# G-CLEF_Shutter_Testing.net
KiCad netlist of a schematic drawn in EAGLE
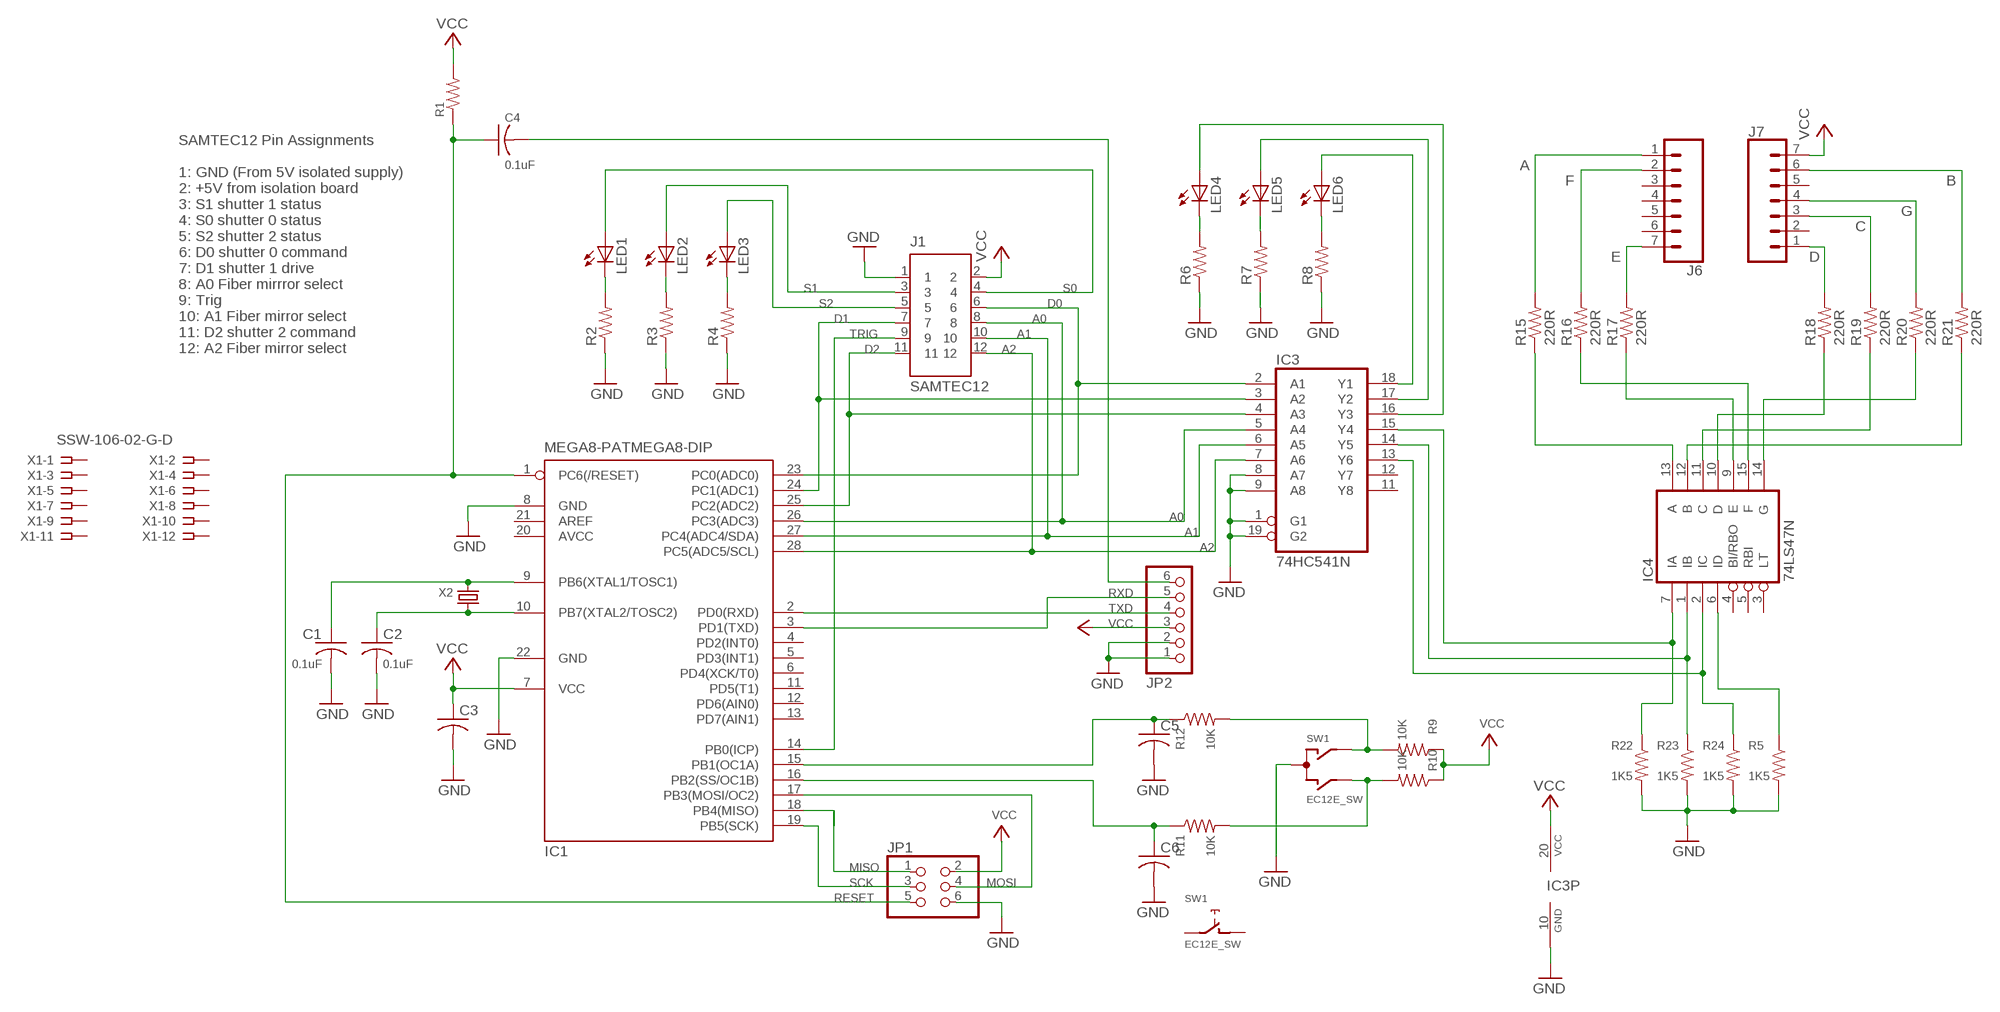
[diagram p0: schematic, sheet 1, part 1 of 2]
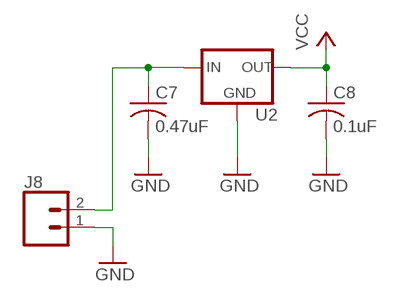
[diagram p1: schematic, sheet 1, part 2 of 2]

(export (version "E")
  (design (tool "Eeschema 10.0.6"))
  (components
    (comp (ref "C1")
      (value "0.1uF")
      (footprint "eagle-import:C025-024X044")
      (libsource (lib "eagle-import") (part "C-US025-024X044"))
    )
    (comp (ref "C2")
      (value "0.1uF")
      (footprint "eagle-import:C025-024X044")
      (libsource (lib "eagle-import") (part "C-US025-024X044"))
    )
    (comp (ref "C3")
      (value "C-US025-024X044")
      (footprint "eagle-import:C025-024X044")
      (libsource (lib "eagle-import") (part "C-US025-024X044"))
    )
    (comp (ref "C4")
      (value "0.1uF")
      (footprint "eagle-import:C025-024X044")
      (libsource (lib "eagle-import") (part "C-US025-024X044"))
    )
    (comp (ref "C5")
      (value "C-US025-024X044")
      (footprint "eagle-import:C025-024X044")
      (libsource (lib "eagle-import") (part "C-US025-024X044"))
    )
    (comp (ref "C6")
      (value "C-US025-024X044")
      (footprint "eagle-import:C025-024X044")
      (libsource (lib "eagle-import") (part "C-US025-024X044"))
    )
    (comp (ref "C7")
      (value "0.47uF")
      (footprint "eagle-import:C050-025X075")
      (libsource (lib "eagle-import") (part "rcl_334_C-US050-025X075"))
    )
    (comp (ref "C8")
      (value "0.1uF")
      (footprint "eagle-import:C050-025X075")
      (libsource (lib "eagle-import") (part "rcl_334_C-US050-025X075"))
    )
    (comp (ref "IC1")
      (value "MEGA8-PATMEGA8-DIP")
      (footprint "eagle-import:DIP762W53P254L3467H457Q28B")
      (libsource (lib "eagle-import") (part "MEGA8-PATMEGA8-DIP"))
    )
    (comp (ref "IC3")
      (value "74HC541N")
      (footprint "eagle-import:DIL20")
      (libsource (lib "eagle-import") (part "74541NLS"))
    )
    (comp (ref "IC4")
      (value "74LS47N")
      (footprint "eagle-import:DIL16")
      (libsource (lib "eagle-import") (part "7447NLS"))
    )
    (comp (ref "J1")
      (value "SAMTEC12")
      (footprint "eagle-import:SAMTEC12")
      (libsource (lib "eagle-import") (part "SAMTEC12"))
    )
    (comp (ref "J6")
      (value "CONN_07")
      (footprint "eagle-import:1X07")
      (libsource (lib "eagle-import") (part "CONN_07"))
    )
    (comp (ref "J7")
      (value "CONN_07")
      (footprint "eagle-import:1X07")
      (libsource (lib "eagle-import") (part "CONN_07"))
    )
    (comp (ref "J8")
      (value "CONN_02")
      (footprint "eagle-import:1X02")
      (libsource (lib "eagle-import") (part "CONN_02"))
    )
    (comp (ref "JP1")
      (value "PINHD-2X3")
      (footprint "eagle-import:2X03")
      (libsource (lib "eagle-import") (part "PINHD-2X3"))
    )
    (comp (ref "JP2")
      (value "PINHD-1X6/90")
      (footprint "eagle-import:1X06_90")
      (libsource (lib "eagle-import") (part "PINHD-1X6/90"))
    )
    (comp (ref "LED1")
      (value "LED5MM")
      (footprint "eagle-import:LED5MM")
      (libsource (lib "eagle-import") (part "LED5MM"))
    )
    (comp (ref "LED2")
      (value "LED5MM")
      (footprint "eagle-import:LED5MM")
      (libsource (lib "eagle-import") (part "LED5MM"))
    )
    (comp (ref "LED3")
      (value "LED5MM")
      (footprint "eagle-import:LED5MM")
      (libsource (lib "eagle-import") (part "LED5MM"))
    )
    (comp (ref "LED4")
      (value "LED5MM")
      (footprint "eagle-import:LED5MM")
      (libsource (lib "eagle-import") (part "LED5MM"))
    )
    (comp (ref "LED5")
      (value "LED5MM")
      (footprint "eagle-import:LED5MM")
      (libsource (lib "eagle-import") (part "LED5MM"))
    )
    (comp (ref "LED6")
      (value "LED5MM")
      (footprint "eagle-import:LED5MM")
      (libsource (lib "eagle-import") (part "LED5MM"))
    )
    (comp (ref "R1")
      (value "R-US_0207/7")
      (footprint "eagle-import:0207_7")
      (libsource (lib "eagle-import") (part "R-US_0207/7"))
    )
    (comp (ref "R2")
      (value "R-US_0207/7")
      (footprint "eagle-import:0207_7")
      (libsource (lib "eagle-import") (part "R-US_0207/7"))
    )
    (comp (ref "R3")
      (value "R-US_0207/7")
      (footprint "eagle-import:0207_7")
      (libsource (lib "eagle-import") (part "R-US_0207/7"))
    )
    (comp (ref "R4")
      (value "R-US_0207/7")
      (footprint "eagle-import:0207_7")
      (libsource (lib "eagle-import") (part "R-US_0207/7"))
    )
    (comp (ref "R5")
      (value "1K5")
      (footprint "eagle-import:0207_7")
      (libsource (lib "eagle-import") (part "rcl_334_R-US_0207/7"))
    )
    (comp (ref "R6")
      (value "R-US_0207/7")
      (footprint "eagle-import:0207_7")
      (libsource (lib "eagle-import") (part "R-US_0207/7"))
    )
    (comp (ref "R7")
      (value "R-US_0207/7")
      (footprint "eagle-import:0207_7")
      (libsource (lib "eagle-import") (part "R-US_0207/7"))
    )
    (comp (ref "R8")
      (value "R-US_0207/7")
      (footprint "eagle-import:0207_7")
      (libsource (lib "eagle-import") (part "R-US_0207/7"))
    )
    (comp (ref "R9")
      (value "10K")
      (footprint "eagle-import:0207_7")
      (libsource (lib "eagle-import") (part "rcl_334_R-US_0207/7"))
    )
    (comp (ref "R10")
      (value "10K")
      (footprint "eagle-import:0207_7")
      (libsource (lib "eagle-import") (part "rcl_334_R-US_0207/7"))
    )
    (comp (ref "R11")
      (value "10K")
      (footprint "eagle-import:0207_7")
      (libsource (lib "eagle-import") (part "rcl_334_R-US_0207/7"))
    )
    (comp (ref "R12")
      (value "10K")
      (footprint "eagle-import:0207_7")
      (libsource (lib "eagle-import") (part "rcl_334_R-US_0207/7"))
    )
    (comp (ref "R15")
      (value "220R")
      (footprint "eagle-import:0207_7")
      (libsource (lib "eagle-import") (part "rcl_334_R-US_0207/7"))
    )
    (comp (ref "R16")
      (value "220R")
      (footprint "eagle-import:0207_7")
      (libsource (lib "eagle-import") (part "rcl_334_R-US_0207/7"))
    )
    (comp (ref "R17")
      (value "220R")
      (footprint "eagle-import:0207_7")
      (libsource (lib "eagle-import") (part "rcl_334_R-US_0207/7"))
    )
    (comp (ref "R18")
      (value "220R")
      (footprint "eagle-import:0207_7")
      (libsource (lib "eagle-import") (part "rcl_334_R-US_0207/7"))
    )
    (comp (ref "R19")
      (value "220R")
      (footprint "eagle-import:0207_7")
      (libsource (lib "eagle-import") (part "rcl_334_R-US_0207/7"))
    )
    (comp (ref "R20")
      (value "220R")
      (footprint "eagle-import:0207_7")
      (libsource (lib "eagle-import") (part "rcl_334_R-US_0207/7"))
    )
    (comp (ref "R21")
      (value "220R")
      (footprint "eagle-import:0207_7")
      (libsource (lib "eagle-import") (part "rcl_334_R-US_0207/7"))
    )
    (comp (ref "R22")
      (value "1K5")
      (footprint "eagle-import:0207_7")
      (libsource (lib "eagle-import") (part "rcl_334_R-US_0207/7"))
    )
    (comp (ref "R23")
      (value "1K5")
      (footprint "eagle-import:0207_7")
      (libsource (lib "eagle-import") (part "rcl_334_R-US_0207/7"))
    )
    (comp (ref "R24")
      (value "1K5")
      (footprint "eagle-import:0207_7")
      (libsource (lib "eagle-import") (part "rcl_334_R-US_0207/7"))
    )
    (comp (ref "SW1")
      (value "EC12E_SW")
      (footprint "eagle-import:ALPS_EC12E_SW")
      (fields (field (name "MPN") "EC12E2424407"))
      (libsource (lib "eagle-import") (part "EC12E_SW"))
    )
    (comp (ref "U2")
      (value "V_REG_78XXSINK")
      (footprint "eagle-import:TO220-IGO")
      (libsource (lib "eagle-import") (part "V_REG_78XXSINK"))
    )
    (comp (ref "X1")
      (value "SSW-106-02-G-D")
      (footprint "eagle-import:SSW-106-02-G-D")
      (fields (field (name "MF") "Samtec Inc."))
      (libsource (lib "eagle-import") (part "SSW-106-02-G-D"))
    )
    (comp (ref "X2")
      (value "CRYSTALS-NOGND-HC49")
      (footprint "eagle-import:HC49")
      (libsource (lib "eagle-import") (part "CRYSTALS-NOGND-HC49"))
    )
  )
  (nets
    (net (code "1") (name "/A") (class "Default")
      (node (ref "J6") (pin "1") (pinfunction "1_1") (pintype "passive"))
      (node (ref "R15") (pin "2") (pinfunction "2_2") (pintype "passive"))
    )
    (net (code "2") (name "/A0") (class "Default")
      (node (ref "IC1") (pin "26") (pinfunction "PC3(ADC3)_26") (pintype "bidirectional"))
      (node (ref "IC3") (pin "5") (pinfunction "A4_5") (pintype "input"))
      (node (ref "J1") (pin "8") (pinfunction "8_8") (pintype "bidirectional"))
    )
    (net (code "3") (name "/A1") (class "Default")
      (node (ref "IC1") (pin "27") (pinfunction "PC4(ADC4/SDA)_27") (pintype "bidirectional"))
      (node (ref "IC3") (pin "6") (pinfunction "A5_6") (pintype "input"))
      (node (ref "J1") (pin "10") (pinfunction "10_10") (pintype "bidirectional"))
    )
    (net (code "4") (name "/A2") (class "Default")
      (node (ref "IC1") (pin "28") (pinfunction "PC5(ADC5/SCL)_28") (pintype "bidirectional"))
      (node (ref "IC3") (pin "7") (pinfunction "A6_7") (pintype "input"))
      (node (ref "J1") (pin "12") (pinfunction "12_12") (pintype "bidirectional"))
    )
    (net (code "5") (name "/AVCC") (class "Default")
      (node (ref "IC1") (pin "20") (pinfunction "AVCC_20") (pintype "power_in"))
    )
    (net (code "6") (name "/B") (class "Default")
      (node (ref "J7") (pin "6") (pinfunction "6_6") (pintype "passive"))
      (node (ref "R21") (pin "2") (pinfunction "2_2") (pintype "passive"))
    )
    (net (code "7") (name "/C") (class "Default")
      (node (ref "J7") (pin "3") (pinfunction "3_3") (pintype "passive"))
      (node (ref "R19") (pin "2") (pinfunction "2_2") (pintype "passive"))
    )
    (net (code "8") (name "/D") (class "Default")
      (node (ref "J7") (pin "1") (pinfunction "1_1") (pintype "passive"))
      (node (ref "R18") (pin "2") (pinfunction "2_2") (pintype "passive"))
    )
    (net (code "9") (name "/D0") (class "Default")
      (node (ref "IC1") (pin "23") (pinfunction "PC0(ADC0)_23") (pintype "bidirectional"))
      (node (ref "IC3") (pin "2") (pinfunction "A1_2") (pintype "input"))
      (node (ref "J1") (pin "6") (pinfunction "6_6") (pintype "bidirectional"))
    )
    (net (code "10") (name "/D1") (class "Default")
      (node (ref "IC1") (pin "24") (pinfunction "PC1(ADC1)_24") (pintype "bidirectional"))
      (node (ref "IC3") (pin "3") (pinfunction "A2_3") (pintype "input"))
      (node (ref "J1") (pin "7") (pinfunction "7_7") (pintype "bidirectional"))
    )
    (net (code "11") (name "/D2") (class "Default")
      (node (ref "IC1") (pin "25") (pinfunction "PC2(ADC2)_25") (pintype "bidirectional"))
      (node (ref "IC3") (pin "4") (pinfunction "A3_4") (pintype "input"))
      (node (ref "J1") (pin "11") (pinfunction "11_11") (pintype "bidirectional"))
    )
    (net (code "12") (name "/E") (class "Default")
      (node (ref "J6") (pin "7") (pinfunction "7_7") (pintype "passive"))
      (node (ref "R17") (pin "2") (pinfunction "2_2") (pintype "passive"))
    )
    (net (code "13") (name "/F") (class "Default")
      (node (ref "J6") (pin "2") (pinfunction "2_2") (pintype "passive"))
      (node (ref "R16") (pin "2") (pinfunction "2_2") (pintype "passive"))
    )
    (net (code "14") (name "/G") (class "Default")
      (node (ref "J7") (pin "4") (pinfunction "4_4") (pintype "passive"))
      (node (ref "R20") (pin "2") (pinfunction "2_2") (pintype "passive"))
    )
    (net (code "15") (name "/MISO") (class "Default")
      (node (ref "IC1") (pin "18") (pinfunction "PB4(MISO)_18") (pintype "bidirectional"))
      (node (ref "JP1") (pin "1") (pinfunction "1_1") (pintype "passive"))
    )
    (net (code "16") (name "/MOSI") (class "Default")
      (node (ref "IC1") (pin "17") (pinfunction "PB3(MOSI/OC2)_17") (pintype "bidirectional"))
      (node (ref "JP1") (pin "4") (pinfunction "4_4") (pintype "passive"))
    )
    (net (code "17") (name "/RESET") (class "Default")
      (node (ref "C4") (pin "1") (pinfunction "1_1") (pintype "passive"))
      (node (ref "IC1") (pin "1") (pinfunction "PC6(/RESET)_1") (pintype "bidirectional"))
      (node (ref "JP1") (pin "5") (pinfunction "5_5") (pintype "passive"))
      (node (ref "R1") (pin "1") (pinfunction "1_1") (pintype "passive"))
    )
    (net (code "18") (name "/RXD") (class "Default")
      (node (ref "IC1") (pin "3") (pinfunction "PD1(TXD)_3") (pintype "bidirectional"))
      (node (ref "JP2") (pin "5") (pinfunction "5_5") (pintype "passive"))
    )
    (net (code "19") (name "/S0") (class "Default")
      (node (ref "J1") (pin "4") (pinfunction "4_4") (pintype "bidirectional"))
      (node (ref "LED1") (pin "A") (pinfunction "A_A") (pintype "passive"))
    )
    (net (code "20") (name "/S1") (class "Default")
      (node (ref "J1") (pin "3") (pinfunction "3_3") (pintype "bidirectional"))
      (node (ref "LED2") (pin "A") (pinfunction "A_A") (pintype "passive"))
    )
    (net (code "21") (name "/S2") (class "Default")
      (node (ref "J1") (pin "5") (pinfunction "5_5") (pintype "bidirectional"))
      (node (ref "LED3") (pin "A") (pinfunction "A_A") (pintype "passive"))
    )
    (net (code "22") (name "/SCK") (class "Default")
      (node (ref "IC1") (pin "19") (pinfunction "PB5(SCK)_19") (pintype "bidirectional"))
      (node (ref "JP1") (pin "3") (pinfunction "3_3") (pintype "passive"))
    )
    (net (code "23") (name "/TRIG") (class "Default")
      (node (ref "IC1") (pin "14") (pinfunction "PB0(ICP)_14") (pintype "bidirectional"))
      (node (ref "J1") (pin "9") (pinfunction "9_9") (pintype "bidirectional"))
    )
    (net (code "24") (name "/TXD") (class "Default")
      (node (ref "IC1") (pin "2") (pinfunction "PD0(RXD)_2") (pintype "bidirectional"))
      (node (ref "JP2") (pin "4") (pinfunction "4_4") (pintype "passive"))
    )
    (net (code "25") (name "GND") (class "Default")
      (node (ref "C1") (pin "2") (pinfunction "2_2") (pintype "passive"))
      (node (ref "C2") (pin "2") (pinfunction "2_2") (pintype "passive"))
      (node (ref "C3") (pin "2") (pinfunction "2_2") (pintype "passive"))
      (node (ref "C5") (pin "2") (pinfunction "2_2") (pintype "passive"))
      (node (ref "C6") (pin "2") (pinfunction "2_2") (pintype "passive"))
      (node (ref "C7") (pin "2") (pinfunction "2_2") (pintype "passive"))
      (node (ref "C8") (pin "2") (pinfunction "2_2") (pintype "passive"))
      (node (ref "IC1") (pin "22") (pinfunction "GND_22") (pintype "power_in"))
      (node (ref "IC1") (pin "8") (pinfunction "GND_8") (pintype "power_in"))
      (node (ref "IC3") (pin "1") (pinfunction "G1_1") (pintype "input"))
      (node (ref "IC3") (pin "10") (pinfunction "GND_10") (pintype "power_in"))
      (node (ref "IC3") (pin "19") (pinfunction "G2_19") (pintype "input"))
      (node (ref "IC3") (pin "8") (pinfunction "A7_8") (pintype "input"))
      (node (ref "IC3") (pin "9") (pinfunction "A8_9") (pintype "input"))
      (node (ref "J1") (pin "1") (pinfunction "1_1") (pintype "bidirectional"))
      (node (ref "J8") (pin "1") (pinfunction "1_1") (pintype "passive"))
      (node (ref "JP1") (pin "6") (pinfunction "6_6") (pintype "passive"))
      (node (ref "JP2") (pin "1") (pinfunction "1_1") (pintype "passive"))
      (node (ref "JP2") (pin "2") (pinfunction "2_2") (pintype "passive"))
      (node (ref "R2") (pin "1") (pinfunction "1_1") (pintype "passive"))
      (node (ref "R22") (pin "2") (pinfunction "2_2") (pintype "passive"))
      (node (ref "R23") (pin "2") (pinfunction "2_2") (pintype "passive"))
      (node (ref "R24") (pin "2") (pinfunction "2_2") (pintype "passive"))
      (node (ref "R3") (pin "1") (pinfunction "1_1") (pintype "passive"))
      (node (ref "R4") (pin "1") (pinfunction "1_1") (pintype "passive"))
      (node (ref "R5") (pin "2") (pinfunction "2_2") (pintype "passive"))
      (node (ref "R6") (pin "1") (pinfunction "1_1") (pintype "passive"))
      (node (ref "R7") (pin "1") (pinfunction "1_1") (pintype "passive"))
      (node (ref "R8") (pin "1") (pinfunction "1_1") (pintype "passive"))
      (node (ref "SW1") (pin "C") (pinfunction "C_C") (pintype "passive"))
      (node (ref "U2") (pin "GND") (pinfunction "GND_GND") (pintype "input"))
    )
    (net (code "26") (name "Net-(C4-Pad2)") (class "Default")
      (node (ref "C4") (pin "2") (pinfunction "2_2") (pintype "passive"))
      (node (ref "JP2") (pin "6") (pinfunction "6_6") (pintype "passive"))
    )
    (net (code "27") (name "Net-(C7-Pad1)") (class "Default")
      (node (ref "C7") (pin "1") (pinfunction "1_1") (pintype "passive"))
      (node (ref "J8") (pin "2") (pinfunction "2_2") (pintype "passive"))
      (node (ref "U2") (pin "IN") (pinfunction "IN_IN") (pintype "input"))
    )
    (net (code "28") (name "Net-(IC1-PB1(OC1A))") (class "Default")
      (node (ref "C5") (pin "1") (pinfunction "1_1") (pintype "passive"))
      (node (ref "IC1") (pin "15") (pinfunction "PB1(OC1A)_15") (pintype "bidirectional"))
      (node (ref "R12") (pin "1") (pinfunction "1_1") (pintype "passive"))
    )
    (net (code "29") (name "Net-(IC1-PB2(SS{slash}OC1B))") (class "Default")
      (node (ref "C6") (pin "1") (pinfunction "1_1") (pintype "passive"))
      (node (ref "IC1") (pin "16") (pinfunction "PB2(SS/OC1B)_16") (pintype "bidirectional"))
      (node (ref "R11") (pin "1") (pinfunction "1_1") (pintype "passive"))
    )
    (net (code "30") (name "Net-(IC1-PB6(XTAL1{slash}TOSC1))") (class "Default")
      (node (ref "C1") (pin "1") (pinfunction "1_1") (pintype "passive"))
      (node (ref "IC1") (pin "9") (pinfunction "PB6(XTAL1/TOSC1)_9") (pintype "bidirectional"))
      (node (ref "X2") (pin "2") (pinfunction "2_2") (pintype "passive"))
    )
    (net (code "31") (name "Net-(IC1-PB7(XTAL2{slash}TOSC2))") (class "Default")
      (node (ref "C2") (pin "1") (pinfunction "1_1") (pintype "passive"))
      (node (ref "IC1") (pin "10") (pinfunction "PB7(XTAL2/TOSC2)_10") (pintype "bidirectional"))
      (node (ref "X2") (pin "1") (pinfunction "1_1") (pintype "passive"))
    )
    (net (code "32") (name "Net-(IC3A-Y1)") (class "Default")
      (node (ref "IC3") (pin "18") (pinfunction "Y1_18") (pintype "tri_state"))
      (node (ref "LED6") (pin "A") (pinfunction "A_A") (pintype "passive"))
    )
    (net (code "33") (name "Net-(IC3A-Y2)") (class "Default")
      (node (ref "IC3") (pin "17") (pinfunction "Y2_17") (pintype "tri_state"))
      (node (ref "LED5") (pin "A") (pinfunction "A_A") (pintype "passive"))
    )
    (net (code "34") (name "Net-(IC3A-Y3)") (class "Default")
      (node (ref "IC3") (pin "16") (pinfunction "Y3_16") (pintype "tri_state"))
      (node (ref "LED4") (pin "A") (pinfunction "A_A") (pintype "passive"))
    )
    (net (code "35") (name "Net-(IC3A-Y4)") (class "Default")
      (node (ref "IC3") (pin "15") (pinfunction "Y4_15") (pintype "tri_state"))
      (node (ref "IC4") (pin "7") (pinfunction "IA_7") (pintype "input"))
      (node (ref "R22") (pin "1") (pinfunction "1_1") (pintype "passive"))
    )
    (net (code "36") (name "Net-(IC3A-Y5)") (class "Default")
      (node (ref "IC3") (pin "14") (pinfunction "Y5_14") (pintype "tri_state"))
      (node (ref "IC4") (pin "1") (pinfunction "IB_1") (pintype "input"))
      (node (ref "R23") (pin "1") (pinfunction "1_1") (pintype "passive"))
    )
    (net (code "37") (name "Net-(IC3A-Y6)") (class "Default")
      (node (ref "IC3") (pin "13") (pinfunction "Y6_13") (pintype "tri_state"))
      (node (ref "IC4") (pin "2") (pinfunction "IC_2") (pintype "input"))
      (node (ref "R24") (pin "1") (pinfunction "1_1") (pintype "passive"))
    )
    (net (code "38") (name "Net-(IC4A-A)") (class "Default")
      (node (ref "IC4") (pin "13") (pinfunction "A_13") (pintype "output"))
      (node (ref "R15") (pin "1") (pinfunction "1_1") (pintype "passive"))
    )
    (net (code "39") (name "Net-(IC4A-B)") (class "Default")
      (node (ref "IC4") (pin "12") (pinfunction "B_12") (pintype "output"))
      (node (ref "R21") (pin "1") (pinfunction "1_1") (pintype "passive"))
    )
    (net (code "40") (name "Net-(IC4A-C)") (class "Default")
      (node (ref "IC4") (pin "11") (pinfunction "C_11") (pintype "output"))
      (node (ref "R19") (pin "1") (pinfunction "1_1") (pintype "passive"))
    )
    (net (code "41") (name "Net-(IC4A-D)") (class "Default")
      (node (ref "IC4") (pin "10") (pinfunction "D_10") (pintype "output"))
      (node (ref "R18") (pin "1") (pinfunction "1_1") (pintype "passive"))
    )
    (net (code "42") (name "Net-(IC4A-E)") (class "Default")
      (node (ref "IC4") (pin "9") (pinfunction "E_9") (pintype "output"))
      (node (ref "R17") (pin "1") (pinfunction "1_1") (pintype "passive"))
    )
    (net (code "43") (name "Net-(IC4A-F)") (class "Default")
      (node (ref "IC4") (pin "15") (pinfunction "F_15") (pintype "output"))
      (node (ref "R16") (pin "1") (pinfunction "1_1") (pintype "passive"))
    )
    (net (code "44") (name "Net-(IC4A-G)") (class "Default")
      (node (ref "IC4") (pin "14") (pinfunction "G_14") (pintype "output"))
      (node (ref "R20") (pin "1") (pinfunction "1_1") (pintype "passive"))
    )
    (net (code "45") (name "Net-(IC4A-ID)") (class "Default")
      (node (ref "IC4") (pin "6") (pinfunction "ID_6") (pintype "input"))
      (node (ref "R5") (pin "1") (pinfunction "1_1") (pintype "passive"))
    )
    (net (code "46") (name "Net-(LED1-C)") (class "Default")
      (node (ref "LED1") (pin "K") (pinfunction "C_K") (pintype "passive"))
      (node (ref "R2") (pin "2") (pinfunction "2_2") (pintype "passive"))
    )
    (net (code "47") (name "Net-(LED2-C)") (class "Default")
      (node (ref "LED2") (pin "K") (pinfunction "C_K") (pintype "passive"))
      (node (ref "R3") (pin "2") (pinfunction "2_2") (pintype "passive"))
    )
    (net (code "48") (name "Net-(LED3-C)") (class "Default")
      (node (ref "LED3") (pin "K") (pinfunction "C_K") (pintype "passive"))
      (node (ref "R4") (pin "2") (pinfunction "2_2") (pintype "passive"))
    )
    (net (code "49") (name "Net-(LED4-C)") (class "Default")
      (node (ref "LED4") (pin "K") (pinfunction "C_K") (pintype "passive"))
      (node (ref "R6") (pin "2") (pinfunction "2_2") (pintype "passive"))
    )
    (net (code "50") (name "Net-(LED5-C)") (class "Default")
      (node (ref "LED5") (pin "K") (pinfunction "C_K") (pintype "passive"))
      (node (ref "R7") (pin "2") (pinfunction "2_2") (pintype "passive"))
    )
    (net (code "51") (name "Net-(LED6-C)") (class "Default")
      (node (ref "LED6") (pin "K") (pinfunction "C_K") (pintype "passive"))
      (node (ref "R8") (pin "2") (pinfunction "2_2") (pintype "passive"))
    )
    (net (code "52") (name "Net-(R10-Pad2)") (class "Default")
      (node (ref "R10") (pin "2") (pinfunction "2_2") (pintype "passive"))
      (node (ref "R11") (pin "2") (pinfunction "2_2") (pintype "passive"))
      (node (ref "SW1") (pin "B") (pinfunction "B_B") (pintype "passive"))
    )
    (net (code "53") (name "Net-(R12-Pad2)") (class "Default")
      (node (ref "R12") (pin "2") (pinfunction "2_2") (pintype "passive"))
      (node (ref "R9") (pin "2") (pinfunction "2_2") (pintype "passive"))
      (node (ref "SW1") (pin "A") (pinfunction "A_A") (pintype "passive"))
    )
    (net (code "54") (name "VCC") (class "Default")
      (node (ref "C3") (pin "1") (pinfunction "1_1") (pintype "passive"))
      (node (ref "C8") (pin "1") (pinfunction "1_1") (pintype "passive"))
      (node (ref "IC1") (pin "7") (pinfunction "VCC_7") (pintype "power_in"))
      (node (ref "IC3") (pin "20") (pinfunction "VCC_20") (pintype "power_in"))
      (node (ref "J1") (pin "2") (pinfunction "2_2") (pintype "bidirectional"))
      (node (ref "J7") (pin "7") (pinfunction "7_7") (pintype "passive"))
      (node (ref "JP1") (pin "2") (pinfunction "2_2") (pintype "passive"))
      (node (ref "JP2") (pin "3") (pinfunction "3_3") (pintype "passive"))
      (node (ref "R1") (pin "2") (pinfunction "2_2") (pintype "passive"))
      (node (ref "R10") (pin "1") (pinfunction "1_1") (pintype "passive"))
      (node (ref "R9") (pin "1") (pinfunction "1_1") (pintype "passive"))
      (node (ref "U2") (pin "OUT") (pinfunction "OUT_OUT") (pintype "passive"))
    )
    (net (code "55") (name "unconnected-(IC1-AREF-Pad21)") (class "Default")
      (node (ref "IC1") (pin "21") (pinfunction "AREF_21") (pintype "passive"))
    )
    (net (code "56") (name "unconnected-(IC1-PD2(INT0)-Pad4)") (class "Default")
      (node (ref "IC1") (pin "4") (pinfunction "PD2(INT0)_4") (pintype "bidirectional"))
    )
    (net (code "57") (name "unconnected-(IC1-PD3(INT1)-Pad5)") (class "Default")
      (node (ref "IC1") (pin "5") (pinfunction "PD3(INT1)_5") (pintype "bidirectional"))
    )
    (net (code "58") (name "unconnected-(IC1-PD4(XCK{slash}T0)-Pad6)") (class "Default")
      (node (ref "IC1") (pin "6") (pinfunction "PD4(XCK/T0)_6") (pintype "bidirectional"))
    )
    (net (code "59") (name "unconnected-(IC1-PD5(T1)-Pad11)") (class "Default")
      (node (ref "IC1") (pin "11") (pinfunction "PD5(T1)_11") (pintype "bidirectional"))
    )
    (net (code "60") (name "unconnected-(IC1-PD6(AIN0)-Pad12)") (class "Default")
      (node (ref "IC1") (pin "12") (pinfunction "PD6(AIN0)_12") (pintype "bidirectional"))
    )
    (net (code "61") (name "unconnected-(IC1-PD7(AIN1)-Pad13)") (class "Default")
      (node (ref "IC1") (pin "13") (pinfunction "PD7(AIN1)_13") (pintype "bidirectional"))
    )
    (net (code "62") (name "unconnected-(IC3A-Y7-Pad12)") (class "Default")
      (node (ref "IC3") (pin "12") (pinfunction "Y7_12") (pintype "tri_state"))
    )
    (net (code "63") (name "unconnected-(IC3A-Y8-Pad11)") (class "Default")
      (node (ref "IC3") (pin "11") (pinfunction "Y8_11") (pintype "tri_state"))
    )
    (net (code "64") (name "unconnected-(IC4A-BI{slash}RBO-Pad4)") (class "Default")
      (node (ref "IC4") (pin "4") (pinfunction "BI/RBO_4") (pintype "input"))
    )
    (net (code "65") (name "unconnected-(IC4A-LT-Pad3)") (class "Default")
      (node (ref "IC4") (pin "3") (pinfunction "LT_3") (pintype "input"))
    )
    (net (code "66") (name "unconnected-(IC4A-RBI-Pad5)") (class "Default")
      (node (ref "IC4") (pin "5") (pinfunction "RBI_5") (pintype "input"))
    )
    (net (code "67") (name "unconnected-(J6-Pad3)") (class "Default")
      (node (ref "J6") (pin "3") (pinfunction "3_3") (pintype "passive"))
    )
    (net (code "68") (name "unconnected-(J6-Pad4)") (class "Default")
      (node (ref "J6") (pin "4") (pinfunction "4_4") (pintype "passive"))
    )
    (net (code "69") (name "unconnected-(J6-Pad5)") (class "Default")
      (node (ref "J6") (pin "5") (pinfunction "5_5") (pintype "passive"))
    )
    (net (code "70") (name "unconnected-(J6-Pad6)") (class "Default")
      (node (ref "J6") (pin "6") (pinfunction "6_6") (pintype "passive"))
    )
    (net (code "71") (name "unconnected-(J7-Pad2)") (class "Default")
      (node (ref "J7") (pin "2") (pinfunction "2_2") (pintype "passive"))
    )
    (net (code "72") (name "unconnected-(J7-Pad5)") (class "Default")
      (node (ref "J7") (pin "5") (pinfunction "5_5") (pintype "passive"))
    )
    (net (code "73") (name "unconnected-(SW1B-1-PadD)") (class "Default")
      (node (ref "SW1") (pin "D") (pinfunction "1_D") (pintype "passive"))
    )
    (net (code "74") (name "unconnected-(SW1B-2-PadE)") (class "Default")
      (node (ref "SW1") (pin "E") (pinfunction "2_E") (pintype "passive"))
    )
    (net (code "75") (name "unconnected-(X1-Pad1)") (class "Default")
      (node (ref "X1") (pin "1") (pinfunction "1_1") (pintype "passive"))
    )
    (net (code "76") (name "unconnected-(X1B-1-Pad10)") (class "Default")
      (node (ref "X1") (pin "10") (pinfunction "1_10") (pintype "passive"))
    )
    (net (code "77") (name "unconnected-(X1C-1-Pad11)") (class "Default")
      (node (ref "X1") (pin "11") (pinfunction "1_11") (pintype "passive"))
    )
    (net (code "78") (name "unconnected-(X1D-1-Pad12)") (class "Default")
      (node (ref "X1") (pin "12") (pinfunction "1_12") (pintype "passive"))
    )
    (net (code "79") (name "unconnected-(X1E-1-Pad2)") (class "Default")
      (node (ref "X1") (pin "2") (pinfunction "1_2") (pintype "passive"))
    )
    (net (code "80") (name "unconnected-(X1F-1-Pad3)") (class "Default")
      (node (ref "X1") (pin "3") (pinfunction "1_3") (pintype "passive"))
    )
    (net (code "81") (name "unconnected-(X1G-1-Pad4)") (class "Default")
      (node (ref "X1") (pin "4") (pinfunction "1_4") (pintype "passive"))
    )
    (net (code "82") (name "unconnected-(X1H-1-Pad5)") (class "Default")
      (node (ref "X1") (pin "5") (pinfunction "1_5") (pintype "passive"))
    )
    (net (code "83") (name "unconnected-(X1I-1-Pad6)") (class "Default")
      (node (ref "X1") (pin "6") (pinfunction "1_6") (pintype "passive"))
    )
    (net (code "84") (name "unconnected-(X1J-1-Pad7)") (class "Default")
      (node (ref "X1") (pin "7") (pinfunction "1_7") (pintype "passive"))
    )
    (net (code "85") (name "unconnected-(X1K-1-Pad8)") (class "Default")
      (node (ref "X1") (pin "8") (pinfunction "1_8") (pintype "passive"))
    )
    (net (code "86") (name "unconnected-(X1L-1-Pad9)") (class "Default")
      (node (ref "X1") (pin "9") (pinfunction "1_9") (pintype "passive"))
    )
  )
)
